# CC2530.net
KiCad netlist of a schematic drawn in Altium Designer
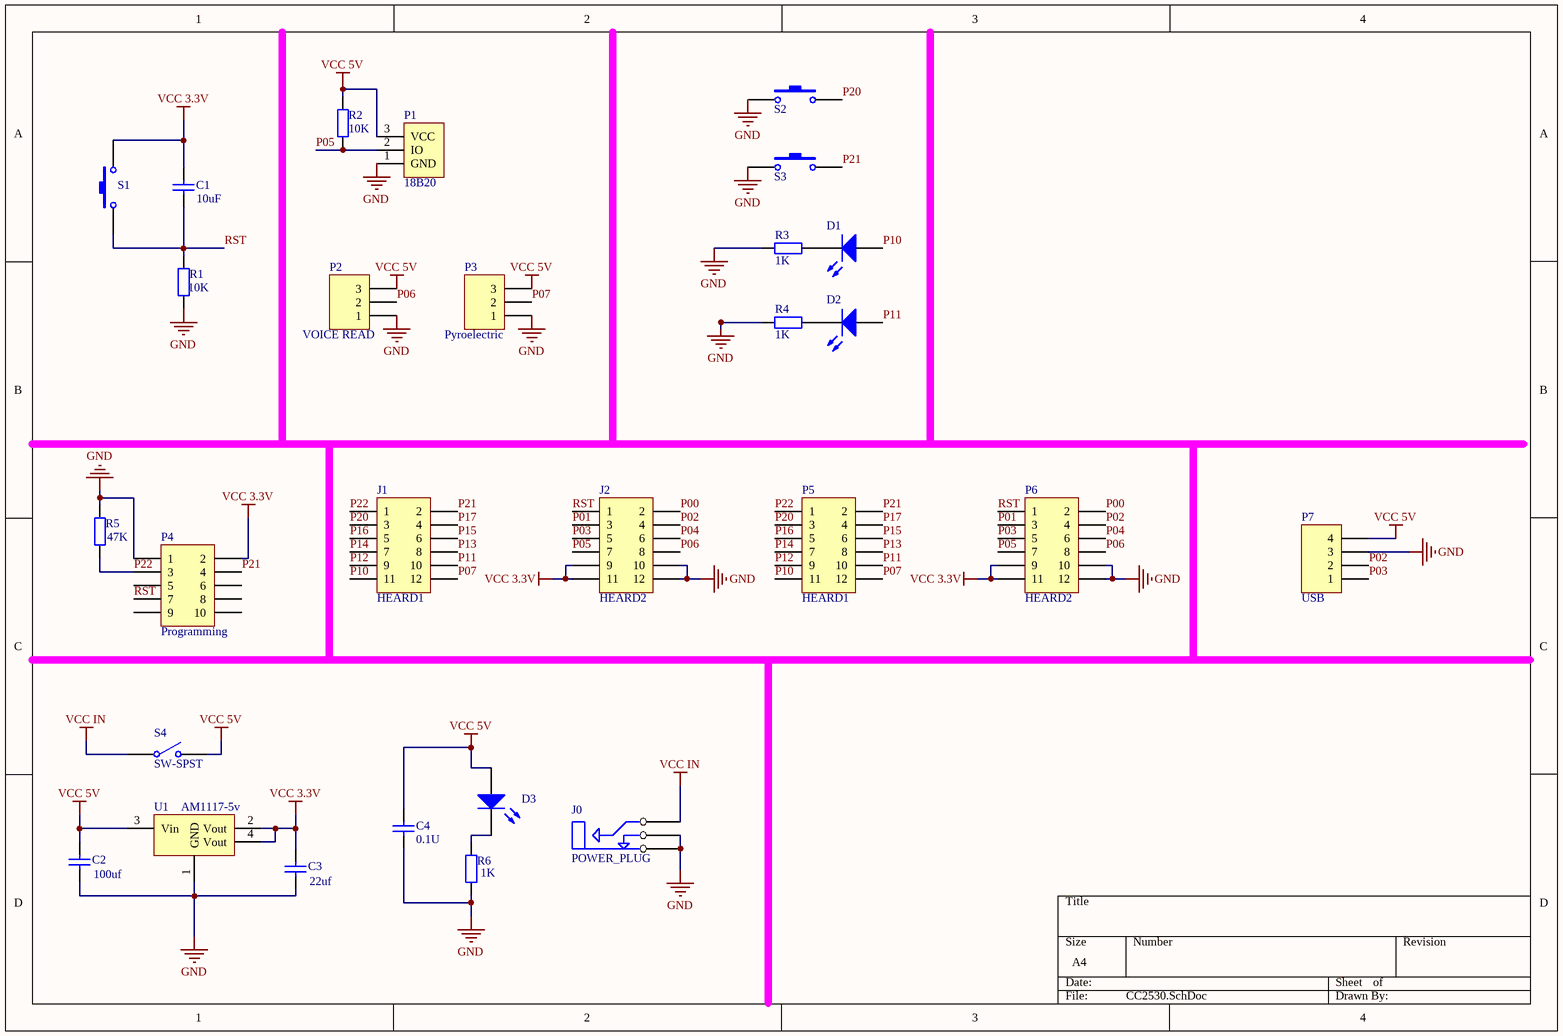
[diagram p0: CC2530.SchDoc]

(export (version "E")
  (design (tool "Eeschema 10.0.6"))
  (components
    (comp (ref "C1")
      (value "10uF")
      (footprint "0805C")
      (description "Capacitor")
      (fields (field (name "Comment") "Cap") (field (name "PUBLISHER") "Altium Limited"))
      (libsource (lib "Miscellaneous Devices") (part "Cap"))
    )
    (comp (ref "C2")
      (value "100uf")
      (footprint "0805C")
      (description "Capacitor")
      (fields (field (name "Comment") "Cap") (field (name "PUBLISHER") "Altium Limited"))
      (libsource (lib "Miscellaneous Devices") (part "Cap"))
    )
    (comp (ref "C3")
      (value "22uf")
      (footprint "0805C")
      (description "Capacitor")
      (fields (field (name "Comment") "Cap") (field (name "PUBLISHER") "Altium Limited"))
      (libsource (lib "Miscellaneous Devices") (part "Cap"))
    )
    (comp (ref "C4")
      (value "0.1U")
      (footprint "0805C")
      (description "Capacitor")
      (fields (field (name "Comment") "Cap") (field (name "PUBLISHER") "Altium Limited"))
      (libsource (lib "Miscellaneous Devices") (part "Cap"))
    )
    (comp (ref "D1")
      (value "LED2")
      (footprint "0805D")
      (description "Typical RED, GREEN, YELLOW, AMBER GaAs LED")
      (fields (field (name "PUBLISHER") "Altium Limited"))
      (libsource (lib "番茄放电器") (part "LED2"))
    )
    (comp (ref "D2")
      (value "LED2")
      (footprint "0805D")
      (description "Typical RED, GREEN, YELLOW, AMBER GaAs LED")
      (fields (field (name "PUBLISHER") "Altium Limited"))
      (libsource (lib "番茄放电器") (part "LED2"))
    )
    (comp (ref "D3")
      (value "LED2")
      (footprint "0805D")
      (description "Typical RED, GREEN, YELLOW, AMBER GaAs LED")
      (fields (field (name "PUBLISHER") "Altium Limited"))
      (libsource (lib "番茄放电器") (part "LED2"))
    )
    (comp (ref "J0") (value "POWER_PLUG") (footprint "POWC") (libsource (lib "番茄放电器") (part "POWER_PLUG")))
    (comp (ref "J1")
      (value "HEARD1")
      (footprint "HDR2X6")
      (description "Header, 6-Pin, Dual row")
      (fields (field (name "PUBLISHER") "Altium Limited"))
      (libsource (lib "Miscellaneous Connectors") (part "MHDR2X6"))
    )
    (comp (ref "J2")
      (value "HEARD2")
      (footprint "HDR2X6")
      (description "Header, 6-Pin, Dual row")
      (fields (field (name "PUBLISHER") "Altium Limited"))
      (libsource (lib "Miscellaneous Connectors") (part "MHDR2X6"))
    )
    (comp (ref "P1")
      (value "18B20")
      (footprint "HDR1X3")
      (description "Header, 3-Pin, Right Angle")
      (fields (field (name "PUBLISHER") "Altium Limited"))
      (libsource (lib "Miscellaneous Connectors") (part "Header 3H"))
    )
    (comp (ref "P2")
      (value "VOICE READ")
      (footprint "HDR1X3")
      (description "Header, 3-Pin")
      (fields (field (name "PUBLISHER") "Altium Limited"))
      (libsource (lib "Miscellaneous Connectors") (part "Header 3"))
    )
    (comp (ref "P3")
      (value "Pyroelectric")
      (footprint "HDR1X3")
      (description "Header, 3-Pin")
      (fields (field (name "PUBLISHER") "Altium Limited"))
      (libsource (lib "Miscellaneous Connectors") (part "Header 3"))
    )
    (comp (ref "P4")
      (value "Programming")
      (footprint "HDR2X5")
      (description "Header, 5-Pin, Dual row")
      (fields (field (name "PUBLISHER") "Altium Limited"))
      (libsource (lib "Miscellaneous Connectors") (part "Header 5X2"))
    )
    (comp (ref "P5")
      (value "HEARD1")
      (footprint "HDR2X6")
      (description "Header, 6-Pin, Dual row")
      (fields (field (name "PUBLISHER") "Altium Limited"))
      (libsource (lib "Miscellaneous Connectors") (part "MHDR2X6"))
    )
    (comp (ref "P6")
      (value "HEARD2")
      (footprint "HDR2X6")
      (description "Header, 6-Pin, Dual row")
      (fields (field (name "PUBLISHER") "Altium Limited"))
      (libsource (lib "Miscellaneous Connectors") (part "MHDR2X6"))
    )
    (comp (ref "P7")
      (value "USB")
      (footprint "HDR1X4")
      (description "Header, 4-Pin")
      (fields (field (name "PUBLISHER") "Altium Limited"))
      (libsource (lib "Miscellaneous Connectors") (part "Header 4"))
    )
    (comp (ref "R1")
      (value "10K")
      (footprint "0805")
      (description "Resistor")
      (fields (field (name "Comment") "Res2") (field (name "PUBLISHER") "Altium Limited"))
      (libsource (lib "Miscellaneous Devices") (part "Res2"))
    )
    (comp (ref "R2")
      (value "10K")
      (footprint "0805")
      (description "Resistor")
      (fields (field (name "Comment") "Res2") (field (name "PUBLISHER") "Altium Limited"))
      (libsource (lib "Miscellaneous Devices") (part "Res2"))
    )
    (comp (ref "R3")
      (value "1K")
      (footprint "0805")
      (description "Resistor")
      (fields (field (name "Comment") "es2") (field (name "PUBLISHER") "Altium Limited"))
      (libsource (lib "番茄放电器") (part "Res2"))
    )
    (comp (ref "R4")
      (value "1K")
      (footprint "0805")
      (description "Resistor")
      (fields (field (name "Comment") "es2") (field (name "PUBLISHER") "Altium Limited"))
      (libsource (lib "番茄放电器") (part "Res2"))
    )
    (comp (ref "R5")
      (value "47K")
      (footprint "0805")
      (description "Resistor")
      (fields (field (name "Comment") "Res2") (field (name "PUBLISHER") "Altium Limited"))
      (libsource (lib "Miscellaneous Devices") (part "Res2"))
    )
    (comp (ref "R6")
      (value "1K")
      (footprint "0805")
      (description "Resistor")
      (fields (field (name "Comment") "Res2") (field (name "PUBLISHER") "Altium Limited"))
      (libsource (lib "Miscellaneous Devices") (part "Res2"))
    )
    (comp (ref "S1")
      (value "SW-PB")
      (footprint "SW-PUSH")
      (description "Switch")
      (fields (field (name "PUBLISHER") "Altium Limited"))
      (libsource (lib "番茄放电器") (part "SW-PB"))
    )
    (comp (ref "S2")
      (value "SW-PB")
      (footprint "SW-PUSH")
      (description "Switch")
      (fields (field (name "PUBLISHER") "Altium Limited"))
      (libsource (lib "番茄放电器") (part "SW-PB"))
    )
    (comp (ref "S3")
      (value "SW-PB")
      (footprint "SW-PUSH")
      (description "Switch")
      (fields (field (name "PUBLISHER") "Altium Limited"))
      (libsource (lib "番茄放电器") (part "SW-PB"))
    )
    (comp (ref "S4")
      (value "SW-SPST")
      (footprint "HDR1X3")
      (description "Single-Pole, Single-Throw Switch")
      (fields (field (name "PUBLISHER") "Altium Limited"))
      (libsource (lib "Miscellaneous Devices") (part "SW-SPST"))
    )
    (comp (ref "U1") (value "AM1117-5v") (footprint "SOT223") (libsource (lib "番茄放电器") (part "LT1085")))
  )
  (nets
    (net (code "1") (name "/P00") (class "Default")
      (node (ref "J2") (pin "2") (pinfunction "2_2") (pintype "passive"))
      (node (ref "P6") (pin "2") (pinfunction "2_2") (pintype "passive"))
    )
    (net (code "2") (name "/P01") (class "Default")
      (node (ref "J2") (pin "3") (pinfunction "3_3") (pintype "passive"))
      (node (ref "P6") (pin "3") (pinfunction "3_3") (pintype "passive"))
    )
    (net (code "3") (name "/P02") (class "Default")
      (node (ref "J2") (pin "4") (pinfunction "4_4") (pintype "passive"))
      (node (ref "P6") (pin "4") (pinfunction "4_4") (pintype "passive"))
      (node (ref "P7") (pin "2") (pinfunction "2_2") (pintype "passive"))
    )
    (net (code "4") (name "/P03") (class "Default")
      (node (ref "J2") (pin "5") (pinfunction "5_5") (pintype "passive"))
      (node (ref "P6") (pin "5") (pinfunction "5_5") (pintype "passive"))
      (node (ref "P7") (pin "1") (pinfunction "1_1") (pintype "passive"))
    )
    (net (code "5") (name "/P04") (class "Default")
      (node (ref "J2") (pin "6") (pinfunction "6_6") (pintype "passive"))
      (node (ref "P6") (pin "6") (pinfunction "6_6") (pintype "passive"))
    )
    (net (code "6") (name "/P05") (class "Default")
      (node (ref "J2") (pin "7") (pinfunction "7_7") (pintype "passive"))
      (node (ref "P1") (pin "2") (pinfunction "IO_2") (pintype "passive"))
      (node (ref "P6") (pin "7") (pinfunction "7_7") (pintype "passive"))
      (node (ref "R2") (pin "1") (pinfunction "1_1") (pintype "passive"))
    )
    (net (code "7") (name "/P06") (class "Default")
      (node (ref "J2") (pin "8") (pinfunction "8_8") (pintype "passive"))
      (node (ref "P2") (pin "2") (pinfunction "2_2") (pintype "passive"))
      (node (ref "P6") (pin "8") (pinfunction "8_8") (pintype "passive"))
    )
    (net (code "8") (name "/P07") (class "Default")
      (node (ref "J1") (pin "12") (pinfunction "12_12") (pintype "passive"))
      (node (ref "P3") (pin "2") (pinfunction "2_2") (pintype "passive"))
      (node (ref "P5") (pin "12") (pinfunction "12_12") (pintype "passive"))
    )
    (net (code "9") (name "/P10") (class "Default")
      (node (ref "D1") (pin "A") (pinfunction "A_A") (pintype "passive"))
      (node (ref "J1") (pin "11") (pinfunction "11_11") (pintype "passive"))
      (node (ref "P5") (pin "11") (pinfunction "11_11") (pintype "passive"))
    )
    (net (code "10") (name "/P11") (class "Default")
      (node (ref "D2") (pin "A") (pinfunction "A_A") (pintype "passive"))
      (node (ref "J1") (pin "10") (pinfunction "10_10") (pintype "passive"))
      (node (ref "P5") (pin "10") (pinfunction "10_10") (pintype "passive"))
    )
    (net (code "11") (name "/P12") (class "Default")
      (node (ref "J1") (pin "9") (pinfunction "9_9") (pintype "passive"))
      (node (ref "P5") (pin "9") (pinfunction "9_9") (pintype "passive"))
    )
    (net (code "12") (name "/P13") (class "Default")
      (node (ref "J1") (pin "8") (pinfunction "8_8") (pintype "passive"))
      (node (ref "P5") (pin "8") (pinfunction "8_8") (pintype "passive"))
    )
    (net (code "13") (name "/P14") (class "Default")
      (node (ref "J1") (pin "7") (pinfunction "7_7") (pintype "passive"))
      (node (ref "P5") (pin "7") (pinfunction "7_7") (pintype "passive"))
    )
    (net (code "14") (name "/P15") (class "Default")
      (node (ref "J1") (pin "6") (pinfunction "6_6") (pintype "passive"))
      (node (ref "P5") (pin "6") (pinfunction "6_6") (pintype "passive"))
    )
    (net (code "15") (name "/P16") (class "Default")
      (node (ref "J1") (pin "5") (pinfunction "5_5") (pintype "passive"))
      (node (ref "P5") (pin "5") (pinfunction "5_5") (pintype "passive"))
    )
    (net (code "16") (name "/P17") (class "Default")
      (node (ref "J1") (pin "4") (pinfunction "4_4") (pintype "passive"))
      (node (ref "P5") (pin "4") (pinfunction "4_4") (pintype "passive"))
    )
    (net (code "17") (name "/P20") (class "Default")
      (node (ref "J1") (pin "3") (pinfunction "3_3") (pintype "passive"))
      (node (ref "P5") (pin "3") (pinfunction "3_3") (pintype "passive"))
      (node (ref "S2") (pin "2") (pinfunction "2_2") (pintype "passive"))
    )
    (net (code "18") (name "/P21") (class "Default")
      (node (ref "J1") (pin "2") (pinfunction "2_2") (pintype "passive"))
      (node (ref "P4") (pin "4") (pinfunction "4_4") (pintype "passive"))
      (node (ref "P5") (pin "2") (pinfunction "2_2") (pintype "passive"))
      (node (ref "S3") (pin "2") (pinfunction "2_2") (pintype "passive"))
    )
    (net (code "19") (name "/P22") (class "Default")
      (node (ref "J1") (pin "1") (pinfunction "1_1") (pintype "passive"))
      (node (ref "P4") (pin "3") (pinfunction "3_3") (pintype "passive"))
      (node (ref "P5") (pin "1") (pinfunction "1_1") (pintype "passive"))
      (node (ref "R5") (pin "1") (pinfunction "1_1") (pintype "passive"))
    )
    (net (code "20") (name "/RST") (class "Default")
      (node (ref "C1") (pin "1") (pinfunction "1_1") (pintype "passive"))
      (node (ref "J2") (pin "1") (pinfunction "1_1") (pintype "passive"))
      (node (ref "P4") (pin "7") (pinfunction "7_7") (pintype "passive"))
      (node (ref "P6") (pin "1") (pinfunction "1_1") (pintype "passive"))
      (node (ref "R1") (pin "2") (pinfunction "2_2") (pintype "passive"))
      (node (ref "S1") (pin "1") (pinfunction "1_1") (pintype "passive"))
    )
    (net (code "21") (name "GND") (class "Default")
      (node (ref "C2") (pin "1") (pinfunction "1_1") (pintype "passive"))
      (node (ref "C3") (pin "1") (pinfunction "1_1") (pintype "passive"))
      (node (ref "C4") (pin "1") (pinfunction "1_1") (pintype "passive"))
      (node (ref "J0") (pin "2") (pinfunction "2_2") (pintype "passive"))
      (node (ref "J0") (pin "3") (pinfunction "3_3") (pintype "passive"))
      (node (ref "J2") (pin "10") (pinfunction "10_10") (pintype "passive"))
      (node (ref "J2") (pin "12") (pinfunction "12_12") (pintype "passive"))
      (node (ref "P1") (pin "1") (pinfunction "GND_1") (pintype "passive"))
      (node (ref "P2") (pin "1") (pinfunction "1_1") (pintype "passive"))
      (node (ref "P3") (pin "1") (pinfunction "1_1") (pintype "passive"))
      (node (ref "P4") (pin "1") (pinfunction "1_1") (pintype "passive"))
      (node (ref "P6") (pin "10") (pinfunction "10_10") (pintype "passive"))
      (node (ref "P6") (pin "12") (pinfunction "12_12") (pintype "passive"))
      (node (ref "P7") (pin "3") (pinfunction "3_3") (pintype "passive"))
      (node (ref "R1") (pin "1") (pinfunction "1_1") (pintype "passive"))
      (node (ref "R3") (pin "1") (pinfunction "1_1") (pintype "passive"))
      (node (ref "R4") (pin "1") (pinfunction "1_1") (pintype "passive"))
      (node (ref "R5") (pin "2") (pinfunction "2_2") (pintype "passive"))
      (node (ref "R6") (pin "1") (pinfunction "1_1") (pintype "passive"))
      (node (ref "S2") (pin "1") (pinfunction "1_1") (pintype "passive"))
      (node (ref "S3") (pin "1") (pinfunction "1_1") (pintype "passive"))
      (node (ref "U1") (pin "1") (pinfunction "GND_1") (pintype "passive"))
    )
    (net (code "22") (name "Net-(D1-PadK)") (class "Default")
      (node (ref "D1") (pin "K") (pinfunction "K_K") (pintype "passive"))
      (node (ref "R3") (pin "2") (pinfunction "2_2") (pintype "passive"))
    )
    (net (code "23") (name "Net-(D2-PadK)") (class "Default")
      (node (ref "D2") (pin "K") (pinfunction "K_K") (pintype "passive"))
      (node (ref "R4") (pin "2") (pinfunction "2_2") (pintype "passive"))
    )
    (net (code "24") (name "Net-(D3-PadK)") (class "Default")
      (node (ref "D3") (pin "K") (pinfunction "K_K") (pintype "passive"))
      (node (ref "R6") (pin "2") (pinfunction "2_2") (pintype "passive"))
    )
    (net (code "25") (name "VCC 3.3V") (class "Default")
      (node (ref "C1") (pin "2") (pinfunction "2_2") (pintype "passive"))
      (node (ref "C3") (pin "2") (pinfunction "2_2") (pintype "passive"))
      (node (ref "J2") (pin "11") (pinfunction "11_11") (pintype "passive"))
      (node (ref "J2") (pin "9") (pinfunction "9_9") (pintype "passive"))
      (node (ref "P4") (pin "2") (pinfunction "2_2") (pintype "passive"))
      (node (ref "P6") (pin "11") (pinfunction "11_11") (pintype "passive"))
      (node (ref "P6") (pin "9") (pinfunction "9_9") (pintype "passive"))
      (node (ref "S1") (pin "2") (pinfunction "2_2") (pintype "passive"))
      (node (ref "U1") (pin "2") (pinfunction "Vout_2") (pintype "passive"))
      (node (ref "U1") (pin "4") (pinfunction "Vout_4") (pintype "passive"))
    )
    (net (code "26") (name "VCC 5V") (class "Default")
      (node (ref "C2") (pin "2") (pinfunction "2_2") (pintype "passive"))
      (node (ref "C4") (pin "2") (pinfunction "2_2") (pintype "passive"))
      (node (ref "D3") (pin "A") (pinfunction "A_A") (pintype "passive"))
      (node (ref "P1") (pin "3") (pinfunction "VCC_3") (pintype "passive"))
      (node (ref "P2") (pin "3") (pinfunction "3_3") (pintype "passive"))
      (node (ref "P3") (pin "3") (pinfunction "3_3") (pintype "passive"))
      (node (ref "P7") (pin "4") (pinfunction "4_4") (pintype "passive"))
      (node (ref "R2") (pin "2") (pinfunction "2_2") (pintype "passive"))
      (node (ref "S4") (pin "2") (pinfunction "NO_2") (pintype "passive"))
      (node (ref "U1") (pin "3") (pinfunction "Vin_3") (pintype "passive"))
    )
    (net (code "27") (name "VCC IN") (class "Default")
      (node (ref "J0") (pin "1") (pinfunction "1_1") (pintype "passive"))
      (node (ref "S4") (pin "1") (pinfunction "COMMON_1") (pintype "passive"))
    )
    (net (code "28") (name "unconnected-(P4-Pad5)") (class "Default")
      (node (ref "P4") (pin "5") (pinfunction "5_5") (pintype "passive"))
    )
    (net (code "29") (name "unconnected-(P4-Pad6)") (class "Default")
      (node (ref "P4") (pin "6") (pinfunction "6_6") (pintype "passive"))
    )
    (net (code "30") (name "unconnected-(P4-Pad8)") (class "Default")
      (node (ref "P4") (pin "8") (pinfunction "8_8") (pintype "passive"))
    )
    (net (code "31") (name "unconnected-(P4-Pad9)") (class "Default")
      (node (ref "P4") (pin "9") (pinfunction "9_9") (pintype "passive"))
    )
    (net (code "32") (name "unconnected-(P4-Pad10)") (class "Default")
      (node (ref "P4") (pin "10") (pinfunction "10_10") (pintype "passive"))
    )
  )
)
